# helios_monitor.net
KiCad netlist of a schematic drawn in EAGLE
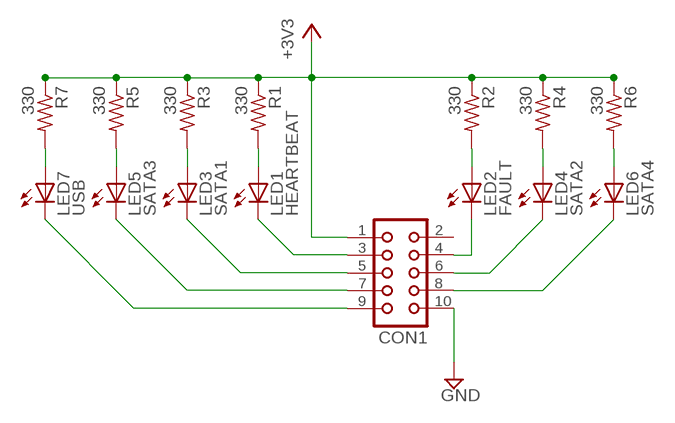
[diagram p0: schematic, sheet 1]

(export (version "E")
  (design (tool "Eeschema 10.0.6"))
  (components
    (comp (ref "CON1")
      (value "CON10")
      (footprint "eagle-import:CON10")
      (libsource (lib "eagle-import") (part "CON10"))
    )
    (comp (ref "LED1")
      (value "HEARTBEAT")
      (footprint "eagle-import:LED5MM")
      (libsource (lib "eagle-import") (part "LED5MM"))
    )
    (comp (ref "LED2")
      (value "FAULT")
      (footprint "eagle-import:LED5MM")
      (libsource (lib "eagle-import") (part "LED5MM"))
    )
    (comp (ref "LED3")
      (value "SATA1")
      (footprint "eagle-import:LED5MM")
      (libsource (lib "eagle-import") (part "LED5MM"))
    )
    (comp (ref "LED4")
      (value "SATA2")
      (footprint "eagle-import:LED5MM")
      (libsource (lib "eagle-import") (part "LED5MM"))
    )
    (comp (ref "LED5")
      (value "SATA3")
      (footprint "eagle-import:LED5MM")
      (libsource (lib "eagle-import") (part "LED5MM"))
    )
    (comp (ref "LED6")
      (value "SATA4")
      (footprint "eagle-import:LED5MM")
      (libsource (lib "eagle-import") (part "LED5MM"))
    )
    (comp (ref "LED7")
      (value "USB")
      (footprint "eagle-import:LED5MM")
      (libsource (lib "eagle-import") (part "LED5MM"))
    )
    (comp (ref "R1")
      (value "330")
      (footprint "eagle-import:0207_10")
      (libsource (lib "eagle-import") (part "R-US_0207/10"))
    )
    (comp (ref "R2")
      (value "330")
      (footprint "eagle-import:0207_10")
      (libsource (lib "eagle-import") (part "R-US_0207/10"))
    )
    (comp (ref "R3")
      (value "330")
      (footprint "eagle-import:0207_10")
      (libsource (lib "eagle-import") (part "R-US_0207/10"))
    )
    (comp (ref "R4")
      (value "330")
      (footprint "eagle-import:0207_10")
      (libsource (lib "eagle-import") (part "R-US_0207/10"))
    )
    (comp (ref "R5")
      (value "330")
      (footprint "eagle-import:0207_10")
      (libsource (lib "eagle-import") (part "R-US_0207/10"))
    )
    (comp (ref "R6")
      (value "330")
      (footprint "eagle-import:0207_10")
      (libsource (lib "eagle-import") (part "R-US_0207/10"))
    )
    (comp (ref "R7")
      (value "330")
      (footprint "eagle-import:0207_10")
      (libsource (lib "eagle-import") (part "R-US_0207/10"))
    )
  )
  (nets
    (net (code "1") (name "+3V3") (class "Default")
      (node (ref "CON1") (pin "1") (pinfunction "1_1") (pintype "passive"))
      (node (ref "R1") (pin "1") (pinfunction "1_1") (pintype "passive"))
      (node (ref "R2") (pin "1") (pinfunction "1_1") (pintype "passive"))
      (node (ref "R3") (pin "1") (pinfunction "1_1") (pintype "passive"))
      (node (ref "R4") (pin "1") (pinfunction "1_1") (pintype "passive"))
      (node (ref "R5") (pin "1") (pinfunction "1_1") (pintype "passive"))
      (node (ref "R6") (pin "1") (pinfunction "1_1") (pintype "passive"))
      (node (ref "R7") (pin "1") (pinfunction "1_1") (pintype "passive"))
    )
    (net (code "2") (name "GND") (class "Default")
      (node (ref "CON1") (pin "10") (pinfunction "10_10") (pintype "passive"))
    )
    (net (code "3") (name "Net-(LED1-C)") (class "Default")
      (node (ref "CON1") (pin "3") (pinfunction "3_3") (pintype "passive"))
      (node (ref "LED1") (pin "K") (pinfunction "C_K") (pintype "passive"))
    )
    (net (code "4") (name "Net-(LED1-PadA)") (class "Default")
      (node (ref "LED1") (pin "A") (pinfunction "A_A") (pintype "passive"))
      (node (ref "R1") (pin "2") (pinfunction "2_2") (pintype "passive"))
    )
    (net (code "5") (name "Net-(LED2-C)") (class "Default")
      (node (ref "CON1") (pin "4") (pinfunction "4_4") (pintype "passive"))
      (node (ref "LED2") (pin "K") (pinfunction "C_K") (pintype "passive"))
    )
    (net (code "6") (name "Net-(LED2-PadA)") (class "Default")
      (node (ref "LED2") (pin "A") (pinfunction "A_A") (pintype "passive"))
      (node (ref "R2") (pin "2") (pinfunction "2_2") (pintype "passive"))
    )
    (net (code "7") (name "Net-(LED3-C)") (class "Default")
      (node (ref "CON1") (pin "5") (pinfunction "5_5") (pintype "passive"))
      (node (ref "LED3") (pin "K") (pinfunction "C_K") (pintype "passive"))
    )
    (net (code "8") (name "Net-(LED3-PadA)") (class "Default")
      (node (ref "LED3") (pin "A") (pinfunction "A_A") (pintype "passive"))
      (node (ref "R3") (pin "2") (pinfunction "2_2") (pintype "passive"))
    )
    (net (code "9") (name "Net-(LED4-C)") (class "Default")
      (node (ref "CON1") (pin "6") (pinfunction "6_6") (pintype "passive"))
      (node (ref "LED4") (pin "K") (pinfunction "C_K") (pintype "passive"))
    )
    (net (code "10") (name "Net-(LED4-PadA)") (class "Default")
      (node (ref "LED4") (pin "A") (pinfunction "A_A") (pintype "passive"))
      (node (ref "R4") (pin "2") (pinfunction "2_2") (pintype "passive"))
    )
    (net (code "11") (name "Net-(LED5-C)") (class "Default")
      (node (ref "CON1") (pin "7") (pinfunction "7_7") (pintype "passive"))
      (node (ref "LED5") (pin "K") (pinfunction "C_K") (pintype "passive"))
    )
    (net (code "12") (name "Net-(LED5-PadA)") (class "Default")
      (node (ref "LED5") (pin "A") (pinfunction "A_A") (pintype "passive"))
      (node (ref "R5") (pin "2") (pinfunction "2_2") (pintype "passive"))
    )
    (net (code "13") (name "Net-(LED6-C)") (class "Default")
      (node (ref "CON1") (pin "8") (pinfunction "8_8") (pintype "passive"))
      (node (ref "LED6") (pin "K") (pinfunction "C_K") (pintype "passive"))
    )
    (net (code "14") (name "Net-(LED6-PadA)") (class "Default")
      (node (ref "LED6") (pin "A") (pinfunction "A_A") (pintype "passive"))
      (node (ref "R6") (pin "2") (pinfunction "2_2") (pintype "passive"))
    )
    (net (code "15") (name "Net-(LED7-C)") (class "Default")
      (node (ref "CON1") (pin "9") (pinfunction "9_9") (pintype "passive"))
      (node (ref "LED7") (pin "K") (pinfunction "C_K") (pintype "passive"))
    )
    (net (code "16") (name "Net-(LED7-PadA)") (class "Default")
      (node (ref "LED7") (pin "A") (pinfunction "A_A") (pintype "passive"))
      (node (ref "R7") (pin "2") (pinfunction "2_2") (pintype "passive"))
    )
    (net (code "17") (name "unconnected-(CON1-Pad2)") (class "Default")
      (node (ref "CON1") (pin "2") (pinfunction "2_2") (pintype "passive"))
    )
  )
)
